# schema.net
KiCad netlist of a schematic drawn in EAGLE
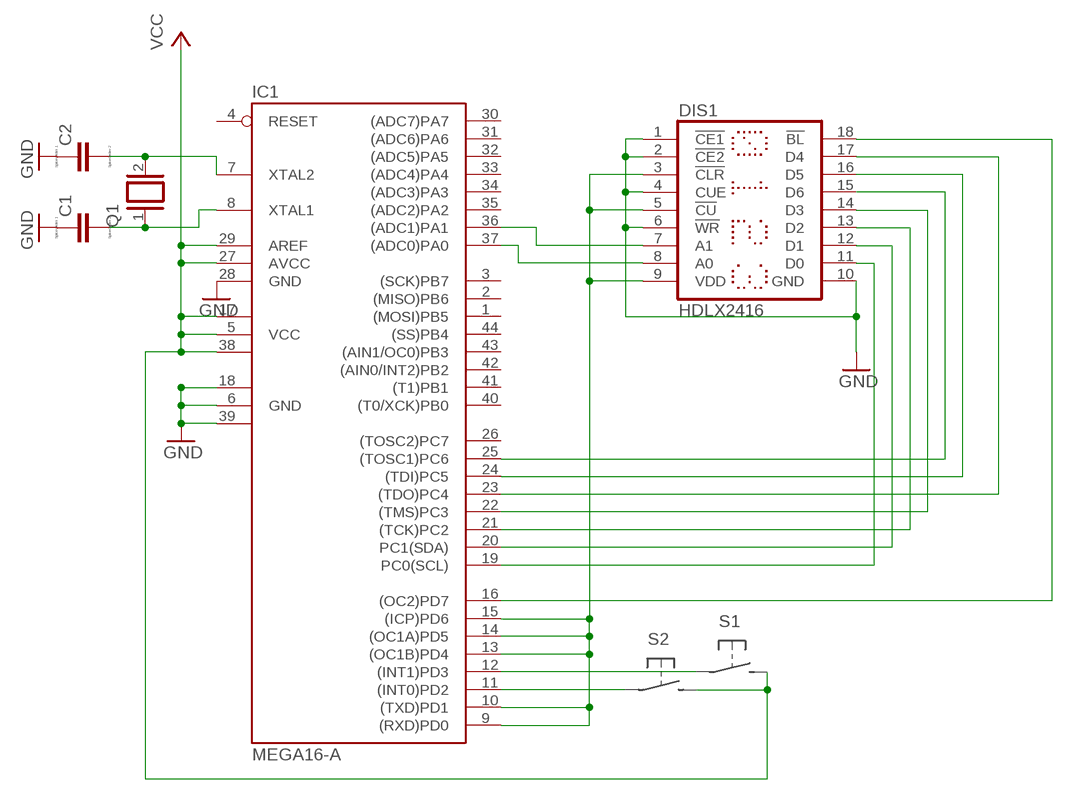
[diagram p0: schematic, sheet 1]

(export (version "E")
  (design (tool "Eeschema 10.0.6"))
  (components
    (comp (ref "C1")
      (value "CC0504")
      (footprint "eagle-import:C0504")
      (libsource (lib "eagle-import") (part "CC0504"))
    )
    (comp (ref "C2")
      (value "CC0504")
      (footprint "eagle-import:C0504")
      (libsource (lib "eagle-import") (part "CC0504"))
    )
    (comp (ref "DIS1")
      (value "HDLX2416")
      (footprint "eagle-import:HDLX2416")
      (libsource (lib "eagle-import") (part "HDLX2416"))
    )
    (comp (ref "IC1")
      (value "MEGA16-A")
      (footprint "eagle-import:TQFP44")
      (fields (field (name "MPN") "ATMEGA16-16AU"))
      (libsource (lib "eagle-import") (part "MEGA16-A"))
    )
    (comp (ref "Q1")
      (value "XTAL")
      (footprint "eagle-import:Q")
      (libsource (lib "eagle-import") (part "XTAL"))
    )
  )
  (nets
    (net (code "1") (name "GND") (class "Default")
      (node (ref "C1") (pin "1") (pinfunction "1_1") (pintype "passive"))
      (node (ref "C2") (pin "1") (pinfunction "1_1") (pintype "passive"))
      (node (ref "DIS1") (pin "1") (pinfunction "~{CE1}_1") (pintype "input"))
      (node (ref "DIS1") (pin "10") (pinfunction "GND_10") (pintype "power_in"))
      (node (ref "DIS1") (pin "2") (pinfunction "~{CE2}_2") (pintype "input"))
      (node (ref "DIS1") (pin "4") (pinfunction "CUE_4") (pintype "input"))
      (node (ref "DIS1") (pin "6") (pinfunction "~{WR}_6") (pintype "input"))
      (node (ref "IC1") (pin "18") (pinfunction "GND1_18") (pintype "power_in"))
      (node (ref "IC1") (pin "28") (pinfunction "GND_28") (pintype "power_in"))
      (node (ref "IC1") (pin "39") (pinfunction "GND2_39") (pintype "power_in"))
      (node (ref "IC1") (pin "6") (pinfunction "GND_6") (pintype "power_in"))
    )
    (net (code "2") (name "Net-(DIS1-A0)") (class "Default")
      (node (ref "DIS1") (pin "8") (pinfunction "A0_8") (pintype "input"))
      (node (ref "IC1") (pin "37") (pinfunction "(ADC0)PA0_37") (pintype "bidirectional"))
    )
    (net (code "3") (name "Net-(DIS1-A1)") (class "Default")
      (node (ref "DIS1") (pin "7") (pinfunction "A1_7") (pintype "input"))
      (node (ref "IC1") (pin "36") (pinfunction "(ADC1)PA1_36") (pintype "bidirectional"))
    )
    (net (code "4") (name "Net-(DIS1-D0)") (class "Default")
      (node (ref "DIS1") (pin "11") (pinfunction "D0_11") (pintype "input"))
      (node (ref "IC1") (pin "19") (pinfunction "PC0(SCL)_19") (pintype "bidirectional"))
    )
    (net (code "5") (name "Net-(DIS1-D1)") (class "Default")
      (node (ref "DIS1") (pin "12") (pinfunction "D1_12") (pintype "input"))
      (node (ref "IC1") (pin "20") (pinfunction "PC1(SDA)_20") (pintype "bidirectional"))
    )
    (net (code "6") (name "Net-(DIS1-D2)") (class "Default")
      (node (ref "DIS1") (pin "13") (pinfunction "D2_13") (pintype "input"))
      (node (ref "IC1") (pin "21") (pinfunction "(TCK)PC2_21") (pintype "bidirectional"))
    )
    (net (code "7") (name "Net-(DIS1-D3)") (class "Default")
      (node (ref "DIS1") (pin "14") (pinfunction "D3_14") (pintype "input"))
      (node (ref "IC1") (pin "22") (pinfunction "(TMS)PC3_22") (pintype "bidirectional"))
    )
    (net (code "8") (name "Net-(DIS1-D4)") (class "Default")
      (node (ref "DIS1") (pin "17") (pinfunction "D4_17") (pintype "input"))
      (node (ref "IC1") (pin "23") (pinfunction "(TDO)PC4_23") (pintype "bidirectional"))
    )
    (net (code "9") (name "Net-(DIS1-D5)") (class "Default")
      (node (ref "DIS1") (pin "16") (pinfunction "D5_16") (pintype "input"))
      (node (ref "IC1") (pin "24") (pinfunction "(TDI)PC5_24") (pintype "bidirectional"))
    )
    (net (code "10") (name "Net-(DIS1-D6)") (class "Default")
      (node (ref "DIS1") (pin "15") (pinfunction "D6_15") (pintype "input"))
      (node (ref "IC1") (pin "25") (pinfunction "(TOSC1)PC6_25") (pintype "bidirectional"))
    )
    (net (code "11") (name "Net-(DIS1-VDD)") (class "Default")
      (node (ref "DIS1") (pin "3") (pinfunction "~{CLR}_3") (pintype "input"))
      (node (ref "DIS1") (pin "5") (pinfunction "~{CU}_5") (pintype "input"))
      (node (ref "DIS1") (pin "9") (pinfunction "VDD_9") (pintype "power_in"))
      (node (ref "IC1") (pin "10") (pinfunction "(TXD)PD1_10") (pintype "bidirectional"))
      (node (ref "IC1") (pin "13") (pinfunction "(OC1B)PD4_13") (pintype "bidirectional"))
      (node (ref "IC1") (pin "14") (pinfunction "(OC1A)PD5_14") (pintype "bidirectional"))
      (node (ref "IC1") (pin "15") (pinfunction "(ICP)PD6_15") (pintype "bidirectional"))
      (node (ref "IC1") (pin "9") (pinfunction "(RXD)PD0_9") (pintype "bidirectional"))
    )
    (net (code "12") (name "Net-(DIS1-~{BL})") (class "Default")
      (node (ref "DIS1") (pin "18") (pinfunction "~{BL}_18") (pintype "input"))
      (node (ref "IC1") (pin "16") (pinfunction "(OC2)PD7_16") (pintype "bidirectional"))
    )
    (net (code "13") (name "Net-(IC1-XTAL1)") (class "Default")
      (node (ref "C1") (pin "2") (pinfunction "2_2") (pintype "passive"))
      (node (ref "IC1") (pin "8") (pinfunction "XTAL1_8") (pintype "bidirectional"))
      (node (ref "Q1") (pin "1") (pinfunction "1_1") (pintype "passive"))
    )
    (net (code "14") (name "Net-(IC1-XTAL2)") (class "Default")
      (node (ref "C2") (pin "2") (pinfunction "2_2") (pintype "passive"))
      (node (ref "IC1") (pin "7") (pinfunction "XTAL2_7") (pintype "bidirectional"))
      (node (ref "Q1") (pin "2") (pinfunction "2_2") (pintype "passive"))
    )
    (net (code "15") (name "VCC") (class "Default")
      (node (ref "IC1") (pin "17") (pinfunction "VCC1_17") (pintype "power_in"))
      (node (ref "IC1") (pin "27") (pinfunction "AVCC_27") (pintype "power_in"))
      (node (ref "IC1") (pin "29") (pinfunction "AREF_29") (pintype "passive"))
      (node (ref "IC1") (pin "38") (pinfunction "VCC2_38") (pintype "power_in"))
      (node (ref "IC1") (pin "5") (pinfunction "VCC_5") (pintype "power_in"))
    )
    (net (code "16") (name "unconnected-(IC1-(ADC2)PA2-Pad35)") (class "Default")
      (node (ref "IC1") (pin "35") (pinfunction "(ADC2)PA2_35") (pintype "bidirectional"))
    )
    (net (code "17") (name "unconnected-(IC1-(ADC3)PA3-Pad34)") (class "Default")
      (node (ref "IC1") (pin "34") (pinfunction "(ADC3)PA3_34") (pintype "bidirectional"))
    )
    (net (code "18") (name "unconnected-(IC1-(ADC4)PA4-Pad33)") (class "Default")
      (node (ref "IC1") (pin "33") (pinfunction "(ADC4)PA4_33") (pintype "bidirectional"))
    )
    (net (code "19") (name "unconnected-(IC1-(ADC5)PA5-Pad32)") (class "Default")
      (node (ref "IC1") (pin "32") (pinfunction "(ADC5)PA5_32") (pintype "bidirectional"))
    )
    (net (code "20") (name "unconnected-(IC1-(ADC6)PA6-Pad31)") (class "Default")
      (node (ref "IC1") (pin "31") (pinfunction "(ADC6)PA6_31") (pintype "bidirectional"))
    )
    (net (code "21") (name "unconnected-(IC1-(ADC7)PA7-Pad30)") (class "Default")
      (node (ref "IC1") (pin "30") (pinfunction "(ADC7)PA7_30") (pintype "bidirectional"))
    )
    (net (code "22") (name "unconnected-(IC1-(AIN0{slash}INT2)PB2-Pad42)") (class "Default")
      (node (ref "IC1") (pin "42") (pinfunction "(AIN0/INT2)PB2_42") (pintype "bidirectional"))
    )
    (net (code "23") (name "unconnected-(IC1-(AIN1{slash}OC0)PB3-Pad43)") (class "Default")
      (node (ref "IC1") (pin "43") (pinfunction "(AIN1/OC0)PB3_43") (pintype "bidirectional"))
    )
    (net (code "24") (name "unconnected-(IC1-(INT0)PD2-Pad11)") (class "Default")
      (node (ref "IC1") (pin "11") (pinfunction "(INT0)PD2_11") (pintype "bidirectional"))
    )
    (net (code "25") (name "unconnected-(IC1-(INT1)PD3-Pad12)") (class "Default")
      (node (ref "IC1") (pin "12") (pinfunction "(INT1)PD3_12") (pintype "bidirectional"))
    )
    (net (code "26") (name "unconnected-(IC1-(MISO)PB6-Pad2)") (class "Default")
      (node (ref "IC1") (pin "2") (pinfunction "(MISO)PB6_2") (pintype "bidirectional"))
    )
    (net (code "27") (name "unconnected-(IC1-(MOSI)PB5-Pad1)") (class "Default")
      (node (ref "IC1") (pin "1") (pinfunction "(MOSI)PB5_1") (pintype "bidirectional"))
    )
    (net (code "28") (name "unconnected-(IC1-(SCK)PB7-Pad3)") (class "Default")
      (node (ref "IC1") (pin "3") (pinfunction "(SCK)PB7_3") (pintype "bidirectional"))
    )
    (net (code "29") (name "unconnected-(IC1-(SS)PB4-Pad44)") (class "Default")
      (node (ref "IC1") (pin "44") (pinfunction "(SS)PB4_44") (pintype "bidirectional"))
    )
    (net (code "30") (name "unconnected-(IC1-(T0{slash}XCK)PB0-Pad40)") (class "Default")
      (node (ref "IC1") (pin "40") (pinfunction "(T0/XCK)PB0_40") (pintype "bidirectional"))
    )
    (net (code "31") (name "unconnected-(IC1-(T1)PB1-Pad41)") (class "Default")
      (node (ref "IC1") (pin "41") (pinfunction "(T1)PB1_41") (pintype "bidirectional"))
    )
    (net (code "32") (name "unconnected-(IC1-(TOSC2)PC7-Pad26)") (class "Default")
      (node (ref "IC1") (pin "26") (pinfunction "(TOSC2)PC7_26") (pintype "bidirectional"))
    )
    (net (code "33") (name "unconnected-(IC1-RESET-Pad4)") (class "Default")
      (node (ref "IC1") (pin "4") (pinfunction "RESET_4") (pintype "input"))
    )
  )
)
